# DRS4_ADC.net
KiCad netlist of a schematic drawn in Altium Designer
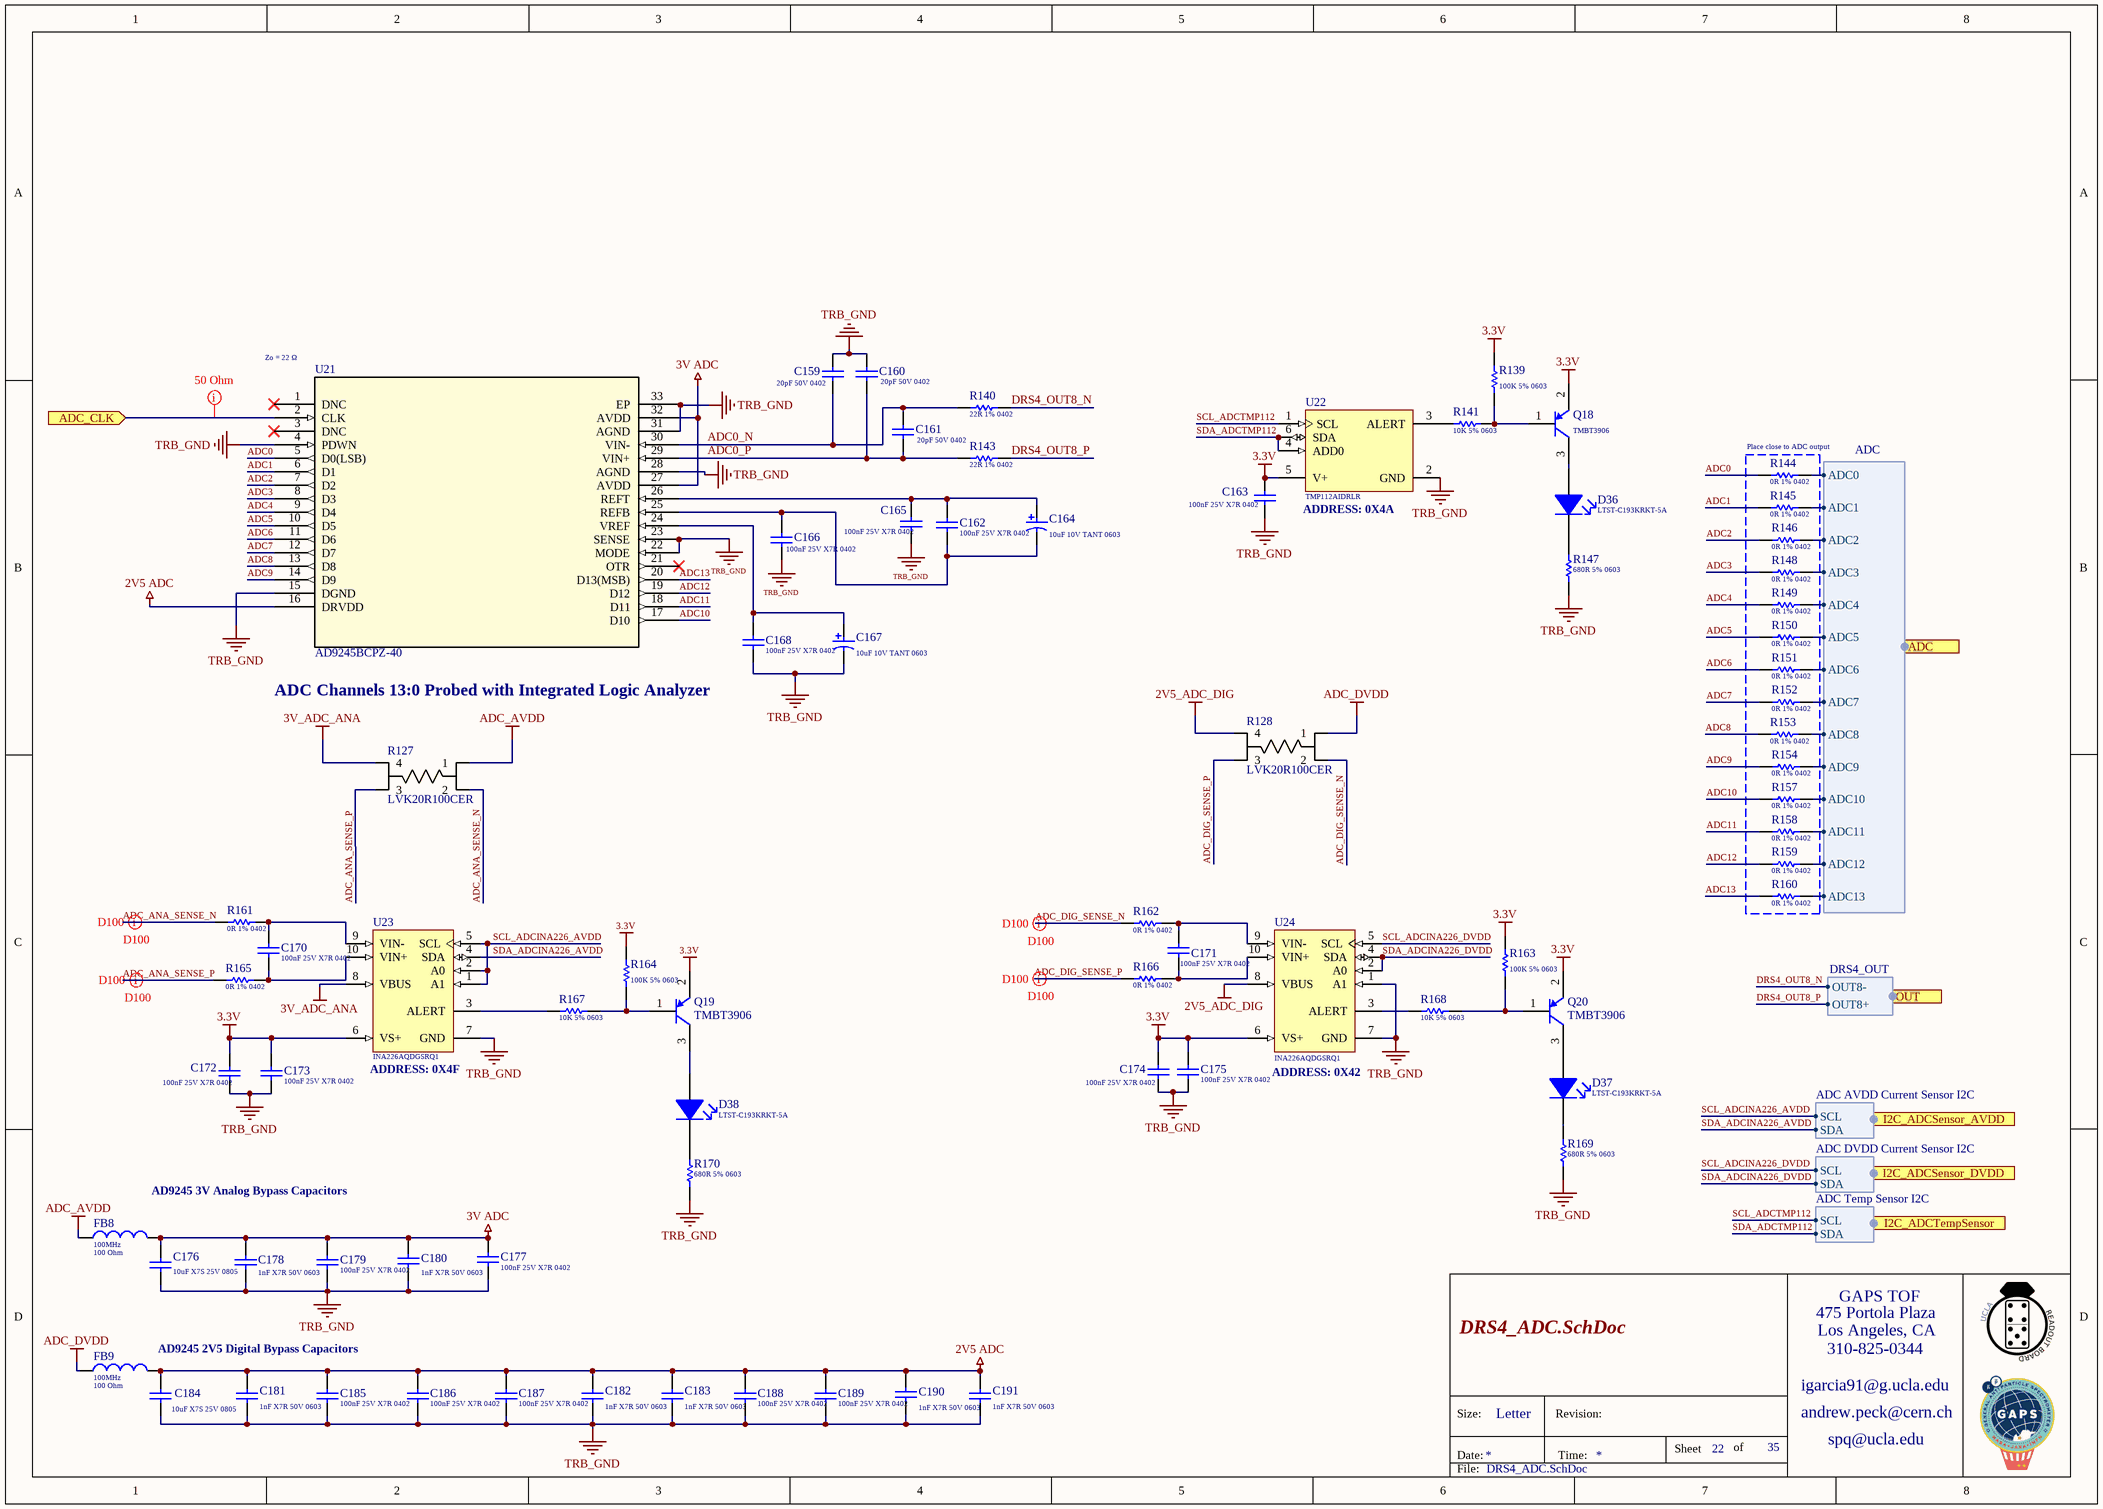
[diagram p0: DRS4_ADC.SchDoc]

(export (version "E")
  (design (tool "Eeschema 10.0.6"))
  (components
    (comp (ref "C159")
      (value "Cap_Murata_GJM1555C1H200GB01D_20pF")
      (footprint "Cap_Murata_GJM1555C1H200GB01D_20pF")
      (description "Multilayer Ceramic Capacitors MLCC - SMD/SMT 0402 20pF 50Volts C0G 2%")
      (fields (field (name "CAPACITANCE") "20pF 50V 0402"))
      (libsource (lib "Cap_Murata_GJM1555C1H200GB01D_20pF") (part "Cap_Murata_GJM1555C1H200GB01D_20pF"))
    )
    (comp (ref "C160")
      (value "Cap_Murata_GJM1555C1H200GB01D_20pF")
      (footprint "Cap_Murata_GJM1555C1H200GB01D_20pF")
      (description "Multilayer Ceramic Capacitors MLCC - SMD/SMT 0402 20pF 50Volts C0G 2%")
      (fields (field (name "CAPACITANCE") "20pF 50V 0402"))
      (libsource (lib "Cap_Murata_GJM1555C1H200GB01D_20pF") (part "Cap_Murata_GJM1555C1H200GB01D_20pF"))
    )
    (comp (ref "C161")
      (value "Cap_Murata_GJM1555C1H200GB01D_20pF")
      (footprint "Cap_Murata_GJM1555C1H200GB01D_20pF")
      (description "Multilayer Ceramic Capacitors MLCC - SMD/SMT 0402 20pF 50Volts C0G 2%")
      (fields (field (name "CAPACITANCE") "20pF 50V 0402"))
      (libsource (lib "Cap_Murata_GJM1555C1H200GB01D_20pF") (part "Cap_Murata_GJM1555C1H200GB01D_20pF"))
    )
    (comp (ref "C162")
      (value "Cap_Taiyo_Yuden_TMK105B7104KV-FR_100nF")
      (footprint "Cap_Taiyo_Yuden_TMK105B7104KV-FR_100nF")
      (description "CAP CER 100nF 25V X7R 0402")
      (fields (field (name "CAPACITANCE") "100nF 25V X7R 0402"))
      (libsource (lib "Cap_Taiyo_Yuden_TMK105B7104KV-FR_100nF") (part "Cap_Taiyo_Yuden_TMK105B7104KV-FR_100nF"))
    )
    (comp (ref "C163")
      (value "Cap_Taiyo_Yuden_TMK105B7104KV-FR_100nF")
      (footprint "Cap_Taiyo_Yuden_TMK105B7104KV-FR_100nF")
      (description "CAP CER 100nF 25V X7R 0402")
      (fields (field (name "CAPACITANCE") "100nF 25V X7R 0402"))
      (libsource (lib "Cap_Taiyo_Yuden_TMK105B7104KV-FR_100nF") (part "Cap_Taiyo_Yuden_TMK105B7104KV-FR_100nF"))
    )
    (comp (ref "C164")
      (value "10uF 10V TANT 0603")
      (footprint "VISH-TR8-M_L")
      (description "Tantalum Capacitor, 10 uF, +/- 20%, 10 V, -55 to 125 degC, 2-Pin SMD (M), RoHS, Tape and Reel")
      (fields (field (name "TOLERANCE") "±20%") (field (name "MANUFACTURER") "Vishay"))
      (libsource (lib "Altium Content Vault") (part "CAP-P-2"))
    )
    (comp (ref "C165")
      (value "Cap_Taiyo_Yuden_TMK105B7104KV-FR_100nF")
      (footprint "Cap_Taiyo_Yuden_TMK105B7104KV-FR_100nF")
      (description "CAP CER 100nF 25V X7R 0402")
      (fields (field (name "CAPACITANCE") "100nF 25V X7R 0402"))
      (libsource (lib "Cap_Taiyo_Yuden_TMK105B7104KV-FR_100nF") (part "Cap_Taiyo_Yuden_TMK105B7104KV-FR_100nF"))
    )
    (comp (ref "C166")
      (value "Cap_Taiyo_Yuden_TMK105B7104KV-FR_100nF")
      (footprint "Cap_Taiyo_Yuden_TMK105B7104KV-FR_100nF")
      (description "CAP CER 100nF 25V X7R 0402")
      (fields (field (name "CAPACITANCE") "100nF 25V X7R 0402"))
      (libsource (lib "Cap_Taiyo_Yuden_TMK105B7104KV-FR_100nF") (part "Cap_Taiyo_Yuden_TMK105B7104KV-FR_100nF"))
    )
    (comp (ref "C167")
      (value "10uF 10V TANT 0603")
      (footprint "VISH-TR8-M_L")
      (description "Tantalum Capacitor, 10 uF, +/- 20%, 10 V, -55 to 125 degC, 2-Pin SMD (M), RoHS, Tape and Reel")
      (fields (field (name "TOLERANCE") "±20%") (field (name "MANUFACTURER") "Vishay"))
      (libsource (lib "Altium Content Vault") (part "CAP-P-2"))
    )
    (comp (ref "C168")
      (value "Cap_Taiyo_Yuden_TMK105B7104KV-FR_100nF")
      (footprint "Cap_Taiyo_Yuden_TMK105B7104KV-FR_100nF")
      (description "CAP CER 100nF 25V X7R 0402")
      (fields (field (name "CAPACITANCE") "100nF 25V X7R 0402"))
      (libsource (lib "Cap_Taiyo_Yuden_TMK105B7104KV-FR_100nF") (part "Cap_Taiyo_Yuden_TMK105B7104KV-FR_100nF"))
    )
    (comp (ref "C170")
      (value "Cap_Taiyo_Yuden_TMK105B7104KV-FR_100nF")
      (footprint "Cap_Taiyo_Yuden_TMK105B7104KV-FR_100nF")
      (description "CAP CER 100nF 25V X7R 0402")
      (fields (field (name "CAPACITANCE") "100nF 25V X7R 0402"))
      (libsource (lib "Cap_Taiyo_Yuden_TMK105B7104KV-FR_100nF") (part "Cap_Taiyo_Yuden_TMK105B7104KV-FR_100nF"))
    )
    (comp (ref "C171")
      (value "Cap_Taiyo_Yuden_TMK105B7104KV-FR_100nF")
      (footprint "Cap_Taiyo_Yuden_TMK105B7104KV-FR_100nF")
      (description "CAP CER 100nF 25V X7R 0402")
      (fields (field (name "CAPACITANCE") "100nF 25V X7R 0402"))
      (libsource (lib "Cap_Taiyo_Yuden_TMK105B7104KV-FR_100nF") (part "Cap_Taiyo_Yuden_TMK105B7104KV-FR_100nF"))
    )
    (comp (ref "C172")
      (value "Cap_Taiyo_Yuden_TMK105B7104KV-FR_100nF")
      (footprint "Cap_Taiyo_Yuden_TMK105B7104KV-FR_100nF")
      (description "CAP CER 100nF 25V X7R 0402")
      (fields (field (name "CAPACITANCE") "100nF 25V X7R 0402"))
      (libsource (lib "Cap_Taiyo_Yuden_TMK105B7104KV-FR_100nF") (part "Cap_Taiyo_Yuden_TMK105B7104KV-FR_100nF"))
    )
    (comp (ref "C173")
      (value "Cap_Taiyo_Yuden_TMK105B7104KV-FR_100nF")
      (footprint "Cap_Taiyo_Yuden_TMK105B7104KV-FR_100nF")
      (description "CAP CER 100nF 25V X7R 0402")
      (fields (field (name "CAPACITANCE") "100nF 25V X7R 0402"))
      (libsource (lib "Cap_Taiyo_Yuden_TMK105B7104KV-FR_100nF") (part "Cap_Taiyo_Yuden_TMK105B7104KV-FR_100nF"))
    )
    (comp (ref "C174")
      (value "Cap_Taiyo_Yuden_TMK105B7104KV-FR_100nF")
      (footprint "Cap_Taiyo_Yuden_TMK105B7104KV-FR_100nF")
      (description "CAP CER 100nF 25V X7R 0402")
      (fields (field (name "CAPACITANCE") "100nF 25V X7R 0402"))
      (libsource (lib "Cap_Taiyo_Yuden_TMK105B7104KV-FR_100nF") (part "Cap_Taiyo_Yuden_TMK105B7104KV-FR_100nF"))
    )
    (comp (ref "C175")
      (value "Cap_Taiyo_Yuden_TMK105B7104KV-FR_100nF")
      (footprint "Cap_Taiyo_Yuden_TMK105B7104KV-FR_100nF")
      (description "CAP CER 100nF 25V X7R 0402")
      (fields (field (name "CAPACITANCE") "100nF 25V X7R 0402"))
      (libsource (lib "Cap_Taiyo_Yuden_TMK105B7104KV-FR_100nF") (part "Cap_Taiyo_Yuden_TMK105B7104KV-FR_100nF"))
    )
    (comp (ref "C176")
      (value "Cap_Murata_ GRM21BC71E106ME11L_10uF")
      (footprint "Cap_Murata_ GRM21BC71E106ME11L_10uF")
      (description "CAP CER 10uF 25V X7R 0805")
      (fields (field (name "CAPACITANCE") "10uF X7S 25V 0805"))
      (libsource (lib "Cap_Murata_ GRM21BC71E106ME11L_10uF") (part "Cap_Murata_ GRM21BC71E106ME11L_10uF"))
    )
    (comp (ref "C177")
      (value "Cap_Taiyo_Yuden_TMK105B7104KV-FR_100nF")
      (footprint "Cap_Taiyo_Yuden_TMK105B7104KV-FR_100nF")
      (description "CAP CER 100nF 25V X7R 0402")
      (fields (field (name "CAPACITANCE") "100nF 25V X7R 0402"))
      (libsource (lib "Cap_Taiyo_Yuden_TMK105B7104KV-FR_100nF") (part "Cap_Taiyo_Yuden_TMK105B7104KV-FR_100nF"))
    )
    (comp (ref "C178")
      (value "Cap_Kemet_C0603C102J5RACAUTO_1nF")
      (footprint "Cap_Kemet_C0603C102J5RACAUTO_1nF")
      (description "CAP CER 1nF 50V X7R 0603")
      (fields (field (name "CAPACITANCE") "1nF X7R 50V 0603"))
      (libsource (lib "Cap_Kemet_C0603C102J5RACAUTO_1nF") (part "Cap_Kemet_C0603C102J5RACAUTO_1nF"))
    )
    (comp (ref "C179")
      (value "Cap_Taiyo_Yuden_TMK105B7104KV-FR_100nF")
      (footprint "Cap_Taiyo_Yuden_TMK105B7104KV-FR_100nF")
      (description "CAP CER 100nF 25V X7R 0402")
      (fields (field (name "CAPACITANCE") "100nF 25V X7R 0402"))
      (libsource (lib "Cap_Taiyo_Yuden_TMK105B7104KV-FR_100nF") (part "Cap_Taiyo_Yuden_TMK105B7104KV-FR_100nF"))
    )
    (comp (ref "C180")
      (value "Cap_Kemet_C0603C102J5RACAUTO_1nF")
      (footprint "Cap_Kemet_C0603C102J5RACAUTO_1nF")
      (description "CAP CER 1nF 50V X7R 0603")
      (fields (field (name "CAPACITANCE") "1nF X7R 50V 0603"))
      (libsource (lib "Cap_Kemet_C0603C102J5RACAUTO_1nF") (part "Cap_Kemet_C0603C102J5RACAUTO_1nF"))
    )
    (comp (ref "C181")
      (value "Cap_Kemet_C0603C102J5RACAUTO_1nF")
      (footprint "Cap_Kemet_C0603C102J5RACAUTO_1nF")
      (description "CAP CER 1nF 50V X7R 0603")
      (fields (field (name "CAPACITANCE") "1nF X7R 50V 0603"))
      (libsource (lib "Cap_Kemet_C0603C102J5RACAUTO_1nF") (part "Cap_Kemet_C0603C102J5RACAUTO_1nF"))
    )
    (comp (ref "C182")
      (value "Cap_Kemet_C0603C102J5RACAUTO_1nF")
      (footprint "Cap_Kemet_C0603C102J5RACAUTO_1nF")
      (description "CAP CER 1nF 50V X7R 0603")
      (fields (field (name "CAPACITANCE") "1nF X7R 50V 0603"))
      (libsource (lib "Cap_Kemet_C0603C102J5RACAUTO_1nF") (part "Cap_Kemet_C0603C102J5RACAUTO_1nF"))
    )
    (comp (ref "C183")
      (value "Cap_Kemet_C0603C102J5RACAUTO_1nF")
      (footprint "Cap_Kemet_C0603C102J5RACAUTO_1nF")
      (description "CAP CER 1nF 50V X7R 0603")
      (fields (field (name "CAPACITANCE") "1nF X7R 50V 0603"))
      (libsource (lib "Cap_Kemet_C0603C102J5RACAUTO_1nF") (part "Cap_Kemet_C0603C102J5RACAUTO_1nF"))
    )
    (comp (ref "C184")
      (value "Cap_Murata_ GRM21BC71E106ME11L_10uF")
      (footprint "Cap_Murata_ GRM21BC71E106ME11L_10uF")
      (description "CAP CER 10uF 25V X7R 0805")
      (fields (field (name "CAPACITANCE") "10uF X7S 25V 0805"))
      (libsource (lib "Cap_Murata_ GRM21BC71E106ME11L_10uF") (part "Cap_Murata_ GRM21BC71E106ME11L_10uF"))
    )
    (comp (ref "C185")
      (value "Cap_Taiyo_Yuden_TMK105B7104KV-FR_100nF")
      (footprint "Cap_Taiyo_Yuden_TMK105B7104KV-FR_100nF")
      (description "CAP CER 100nF 25V X7R 0402")
      (fields (field (name "CAPACITANCE") "100nF 25V X7R 0402"))
      (libsource (lib "Cap_Taiyo_Yuden_TMK105B7104KV-FR_100nF") (part "Cap_Taiyo_Yuden_TMK105B7104KV-FR_100nF"))
    )
    (comp (ref "C186")
      (value "Cap_Taiyo_Yuden_TMK105B7104KV-FR_100nF")
      (footprint "Cap_Taiyo_Yuden_TMK105B7104KV-FR_100nF")
      (description "CAP CER 100nF 25V X7R 0402")
      (fields (field (name "CAPACITANCE") "100nF 25V X7R 0402"))
      (libsource (lib "Cap_Taiyo_Yuden_TMK105B7104KV-FR_100nF") (part "Cap_Taiyo_Yuden_TMK105B7104KV-FR_100nF"))
    )
    (comp (ref "C187")
      (value "Cap_Taiyo_Yuden_TMK105B7104KV-FR_100nF")
      (footprint "Cap_Taiyo_Yuden_TMK105B7104KV-FR_100nF")
      (description "CAP CER 100nF 25V X7R 0402")
      (fields (field (name "CAPACITANCE") "100nF 25V X7R 0402"))
      (libsource (lib "Cap_Taiyo_Yuden_TMK105B7104KV-FR_100nF") (part "Cap_Taiyo_Yuden_TMK105B7104KV-FR_100nF"))
    )
    (comp (ref "C188")
      (value "Cap_Taiyo_Yuden_TMK105B7104KV-FR_100nF")
      (footprint "Cap_Taiyo_Yuden_TMK105B7104KV-FR_100nF")
      (description "CAP CER 100nF 25V X7R 0402")
      (fields (field (name "CAPACITANCE") "100nF 25V X7R 0402"))
      (libsource (lib "Cap_Taiyo_Yuden_TMK105B7104KV-FR_100nF") (part "Cap_Taiyo_Yuden_TMK105B7104KV-FR_100nF"))
    )
    (comp (ref "C189")
      (value "Cap_Taiyo_Yuden_TMK105B7104KV-FR_100nF")
      (footprint "Cap_Taiyo_Yuden_TMK105B7104KV-FR_100nF")
      (description "CAP CER 100nF 25V X7R 0402")
      (fields (field (name "CAPACITANCE") "100nF 25V X7R 0402"))
      (libsource (lib "Cap_Taiyo_Yuden_TMK105B7104KV-FR_100nF") (part "Cap_Taiyo_Yuden_TMK105B7104KV-FR_100nF"))
    )
    (comp (ref "C190")
      (value "Cap_Kemet_C0603C102J5RACAUTO_1nF")
      (footprint "Cap_Kemet_C0603C102J5RACAUTO_1nF")
      (description "CAP CER 1nF 50V X7R 0603")
      (fields (field (name "CAPACITANCE") "1nF X7R 50V 0603"))
      (libsource (lib "Cap_Kemet_C0603C102J5RACAUTO_1nF") (part "Cap_Kemet_C0603C102J5RACAUTO_1nF"))
    )
    (comp (ref "C191")
      (value "Cap_Kemet_C0603C102J5RACAUTO_1nF")
      (footprint "Cap_Kemet_C0603C102J5RACAUTO_1nF")
      (description "CAP CER 1nF 50V X7R 0603")
      (fields (field (name "CAPACITANCE") "1nF X7R 50V 0603"))
      (libsource (lib "Cap_Kemet_C0603C102J5RACAUTO_1nF") (part "Cap_Kemet_C0603C102J5RACAUTO_1nF"))
    )
    (comp (ref "D36")
      (value "LTST-C193KRKT-5A")
      (footprint "Led_Lite-On_LTST-C193KGKT-5A_Red")
      (description "Standard LEDs - SMD Red 470nm 28mcd 20mA")
      (fields (field (name "SERIES") "LTST-C193KRKT-5A"))
      (libsource (lib "Led_Lite-On_LTST-C193KGKT-5A_Red") (part "Led_Lite-On_LTST-C193KGKT-5A_Red"))
    )
    (comp (ref "D37")
      (value "LTST-C193KRKT-5A")
      (footprint "Led_Lite-On_LTST-C193KGKT-5A_Red")
      (description "Standard LEDs - SMD Red 470nm 28mcd 20mA")
      (fields (field (name "SERIES") "LTST-C193KRKT-5A"))
      (libsource (lib "Led_Lite-On_LTST-C193KGKT-5A_Red") (part "Led_Lite-On_LTST-C193KGKT-5A_Red"))
    )
    (comp (ref "D38")
      (value "LTST-C193KRKT-5A")
      (footprint "Led_Lite-On_LTST-C193KGKT-5A_Red")
      (description "Standard LEDs - SMD Red 470nm 28mcd 20mA")
      (fields (field (name "SERIES") "LTST-C193KRKT-5A"))
      (libsource (lib "Led_Lite-On_LTST-C193KGKT-5A_Red") (part "Led_Lite-On_LTST-C193KGKT-5A_Red"))
    )
    (comp (ref "FB8")
      (value "742792731")
      (footprint "FB_Wurth_Electronics_742792731_100Ohms")
      (description "FB SMD 100 OHM 25% 1.2A 0402")
      (fields (field (name "MEASURING FREQUENCY") "100MHz") (field (name "IMPEDANCE") "100 Ohm"))
      (libsource (lib "FB_Wurth_Electronics_742792731_100Ohms") (part "FB_Wurth_Electronics_742792731_100Ohms"))
    )
    (comp (ref "FB9")
      (value "742792731")
      (footprint "FB_Wurth_Electronics_742792731_100Ohms")
      (description "FB SMD 100 OHM 25% 1.2A 0402")
      (fields (field (name "MEASURING FREQUENCY") "100MHz") (field (name "IMPEDANCE") "100 Ohm"))
      (libsource (lib "FB_Wurth_Electronics_742792731_100Ohms") (part "FB_Wurth_Electronics_742792731_100Ohms"))
    )
    (comp (ref "Q18")
      (value "BJT_PNP_Toshiba_TMBT3906")
      (footprint "BJT_PNP_Toshiba_TMBT3906")
      (description "Bipolar Transistors - BJT Transistor for Low Freq. Amplification")
      (fields (field (name "SERIES") "TMBT3906") (field (name "MANUFACTURER") "Toshiba"))
      (libsource (lib "BJT_PNP_Toshiba_TMBT3906") (part "BJT_PNP_Toshiba_TMBT3906"))
    )
    (comp (ref "Q19")
      (value "BJT_PNP_Toshiba_TMBT3906")
      (footprint "BJT_PNP_Toshiba_TMBT3906")
      (description "Bipolar Transistors - BJT Transistor for Low Freq. Amplification")
      (fields (field (name "SERIES") "TMBT3906") (field (name "MANUFACTURER") "Toshiba"))
      (libsource (lib "BJT_PNP_Toshiba_TMBT3906") (part "BJT_PNP_Toshiba_TMBT3906"))
    )
    (comp (ref "Q20")
      (value "BJT_PNP_Toshiba_TMBT3906")
      (footprint "BJT_PNP_Toshiba_TMBT3906")
      (description "Bipolar Transistors - BJT Transistor for Low Freq. Amplification")
      (fields (field (name "SERIES") "TMBT3906") (field (name "MANUFACTURER") "Toshiba"))
      (libsource (lib "BJT_PNP_Toshiba_TMBT3906") (part "BJT_PNP_Toshiba_TMBT3906"))
    )
    (comp (ref "R127")
      (value "LVK20R100CER")
      (footprint "OH_LVK20_OHM")
      (description "Current Sense Resistors - SMD .1 OHM.25% 3/4W")
      (fields (field (name "COPYRIGHT") "Copyright (C) 2018 Accelerated Designs. All rights reserved"))
      (libsource (lib "Shunt_Res_Ohmite_LVK20R100CER") (part "LVK20R100CER"))
    )
    (comp (ref "R128")
      (value "LVK20R100CER")
      (footprint "OH_LVK20_OHM")
      (description "Current Sense Resistors - SMD .1 OHM.25% 3/4W")
      (fields (field (name "COPYRIGHT") "Copyright (C) 2018 Accelerated Designs. All rights reserved"))
      (libsource (lib "Shunt_Res_Ohmite_LVK20R100CER") (part "LVK20R100CER"))
    )
    (comp (ref "R139")
      (value "100K 5% 0603")
      (footprint "RESC0603(1608)_N")
      (description "100K 0.1W 5% 0603 (1608 Metric)  SMD")
      (fields (field (name "TOLERANCE") "5 %") (field (name "POWER") "0.1 W"))
      (libsource (lib "Altium Content Vault") (part "RES"))
    )
    (comp (ref "R140")
      (value "22R 1% 0402")
      (footprint "RESC0402(1005)_L")
      (description "22R 0.063W 1% 0402 (1005 Metric)  SMD")
      (fields (field (name "TOLERANCE") "1 %") (field (name "POWER") "0.063 W"))
      (libsource (lib "Altium Content Vault") (part "RES"))
    )
    (comp (ref "R141")
      (value "10K 5% 0603")
      (footprint "RESC0603(1608)_L")
      (description "10K 0.1W 5% 0603 (1608 Metric)  SMD")
      (fields (field (name "TOLERANCE") "5 %") (field (name "POWER") "0.1 W"))
      (libsource (lib "Altium Content Vault") (part "RES"))
    )
    (comp (ref "R143")
      (value "22R 1% 0402")
      (footprint "RESC0402(1005)_L")
      (description "22R 0.063W 1% 0402 (1005 Metric)  SMD")
      (fields (field (name "TOLERANCE") "1 %") (field (name "POWER") "0.063 W"))
      (libsource (lib "Altium Content Vault") (part "RES"))
    )
    (comp (ref "R144")
      (value "Res_Vishay_CRCW04020000Z0EDC_0_Ohm")
      (footprint "Res_Vishay_CRCW04020000Z0EDC_0_Ohm")
      (description "0R 0.062W 1% 0402 (1005 Metric)  SMD")
      (fields (field (name "RESISTANCE") "0R 1% 0402"))
      (libsource (lib "Res_Vishay_CRCW04020000Z0EDC_0_Ohm") (part "Res_Vishay_CRCW04020000Z0EDC_0_Ohm"))
    )
    (comp (ref "R145")
      (value "Res_Vishay_CRCW04020000Z0EDC_0_Ohm")
      (footprint "Res_Vishay_CRCW04020000Z0EDC_0_Ohm")
      (description "0R 0.062W 1% 0402 (1005 Metric)  SMD")
      (fields (field (name "RESISTANCE") "0R 1% 0402"))
      (libsource (lib "Res_Vishay_CRCW04020000Z0EDC_0_Ohm") (part "Res_Vishay_CRCW04020000Z0EDC_0_Ohm"))
    )
    (comp (ref "R146")
      (value "Res_Vishay_CRCW04020000Z0EDC_0_Ohm")
      (footprint "Res_Vishay_CRCW04020000Z0EDC_0_Ohm")
      (description "0R 0.062W 1% 0402 (1005 Metric)  SMD")
      (fields (field (name "RESISTANCE") "0R 1% 0402"))
      (libsource (lib "Res_Vishay_CRCW04020000Z0EDC_0_Ohm") (part "Res_Vishay_CRCW04020000Z0EDC_0_Ohm"))
    )
    (comp (ref "R147")
      (value "680R 5% 0603")
      (footprint "RESC0603(1608)_L")
      (description "680R 0.1W 5% 0603 (1608 Metric)  SMD")
      (fields (field (name "TOLERANCE") "5 %") (field (name "POWER") "0.1 W"))
      (libsource (lib "Altium Content Vault") (part "RES"))
    )
    (comp (ref "R148")
      (value "Res_Vishay_CRCW04020000Z0EDC_0_Ohm")
      (footprint "Res_Vishay_CRCW04020000Z0EDC_0_Ohm")
      (description "0R 0.062W 1% 0402 (1005 Metric)  SMD")
      (fields (field (name "RESISTANCE") "0R 1% 0402"))
      (libsource (lib "Res_Vishay_CRCW04020000Z0EDC_0_Ohm") (part "Res_Vishay_CRCW04020000Z0EDC_0_Ohm"))
    )
    (comp (ref "R149")
      (value "Res_Vishay_CRCW04020000Z0EDC_0_Ohm")
      (footprint "Res_Vishay_CRCW04020000Z0EDC_0_Ohm")
      (description "0R 0.062W 1% 0402 (1005 Metric)  SMD")
      (fields (field (name "RESISTANCE") "0R 1% 0402"))
      (libsource (lib "Res_Vishay_CRCW04020000Z0EDC_0_Ohm") (part "Res_Vishay_CRCW04020000Z0EDC_0_Ohm"))
    )
    (comp (ref "R150")
      (value "Res_Vishay_CRCW04020000Z0EDC_0_Ohm")
      (footprint "Res_Vishay_CRCW04020000Z0EDC_0_Ohm")
      (description "0R 0.062W 1% 0402 (1005 Metric)  SMD")
      (fields (field (name "RESISTANCE") "0R 1% 0402"))
      (libsource (lib "Res_Vishay_CRCW04020000Z0EDC_0_Ohm") (part "Res_Vishay_CRCW04020000Z0EDC_0_Ohm"))
    )
    (comp (ref "R151")
      (value "Res_Vishay_CRCW04020000Z0EDC_0_Ohm")
      (footprint "Res_Vishay_CRCW04020000Z0EDC_0_Ohm")
      (description "0R 0.062W 1% 0402 (1005 Metric)  SMD")
      (fields (field (name "RESISTANCE") "0R 1% 0402"))
      (libsource (lib "Res_Vishay_CRCW04020000Z0EDC_0_Ohm") (part "Res_Vishay_CRCW04020000Z0EDC_0_Ohm"))
    )
    (comp (ref "R152")
      (value "Res_Vishay_CRCW04020000Z0EDC_0_Ohm")
      (footprint "Res_Vishay_CRCW04020000Z0EDC_0_Ohm")
      (description "0R 0.062W 1% 0402 (1005 Metric)  SMD")
      (fields (field (name "RESISTANCE") "0R 1% 0402"))
      (libsource (lib "Res_Vishay_CRCW04020000Z0EDC_0_Ohm") (part "Res_Vishay_CRCW04020000Z0EDC_0_Ohm"))
    )
    (comp (ref "R153")
      (value "Res_Vishay_CRCW04020000Z0EDC_0_Ohm")
      (footprint "Res_Vishay_CRCW04020000Z0EDC_0_Ohm")
      (description "0R 0.062W 1% 0402 (1005 Metric)  SMD")
      (fields (field (name "RESISTANCE") "0R 1% 0402"))
      (libsource (lib "Res_Vishay_CRCW04020000Z0EDC_0_Ohm") (part "Res_Vishay_CRCW04020000Z0EDC_0_Ohm"))
    )
    (comp (ref "R154")
      (value "Res_Vishay_CRCW04020000Z0EDC_0_Ohm")
      (footprint "Res_Vishay_CRCW04020000Z0EDC_0_Ohm")
      (description "0R 0.062W 1% 0402 (1005 Metric)  SMD")
      (fields (field (name "RESISTANCE") "0R 1% 0402"))
      (libsource (lib "Res_Vishay_CRCW04020000Z0EDC_0_Ohm") (part "Res_Vishay_CRCW04020000Z0EDC_0_Ohm"))
    )
    (comp (ref "R157")
      (value "Res_Vishay_CRCW04020000Z0EDC_0_Ohm")
      (footprint "Res_Vishay_CRCW04020000Z0EDC_0_Ohm")
      (description "0R 0.062W 1% 0402 (1005 Metric)  SMD")
      (fields (field (name "RESISTANCE") "0R 1% 0402"))
      (libsource (lib "Res_Vishay_CRCW04020000Z0EDC_0_Ohm") (part "Res_Vishay_CRCW04020000Z0EDC_0_Ohm"))
    )
    (comp (ref "R158")
      (value "Res_Vishay_CRCW04020000Z0EDC_0_Ohm")
      (footprint "Res_Vishay_CRCW04020000Z0EDC_0_Ohm")
      (description "0R 0.062W 1% 0402 (1005 Metric)  SMD")
      (fields (field (name "RESISTANCE") "0R 1% 0402"))
      (libsource (lib "Res_Vishay_CRCW04020000Z0EDC_0_Ohm") (part "Res_Vishay_CRCW04020000Z0EDC_0_Ohm"))
    )
    (comp (ref "R159")
      (value "Res_Vishay_CRCW04020000Z0EDC_0_Ohm")
      (footprint "Res_Vishay_CRCW04020000Z0EDC_0_Ohm")
      (description "0R 0.062W 1% 0402 (1005 Metric)  SMD")
      (fields (field (name "RESISTANCE") "0R 1% 0402"))
      (libsource (lib "Res_Vishay_CRCW04020000Z0EDC_0_Ohm") (part "Res_Vishay_CRCW04020000Z0EDC_0_Ohm"))
    )
    (comp (ref "R160")
      (value "Res_Vishay_CRCW04020000Z0EDC_0_Ohm")
      (footprint "Res_Vishay_CRCW04020000Z0EDC_0_Ohm")
      (description "0R 0.062W 1% 0402 (1005 Metric)  SMD")
      (fields (field (name "RESISTANCE") "0R 1% 0402"))
      (libsource (lib "Res_Vishay_CRCW04020000Z0EDC_0_Ohm") (part "Res_Vishay_CRCW04020000Z0EDC_0_Ohm"))
    )
    (comp (ref "R161")
      (value "Res_Vishay_CRCW04020000Z0EDC_0_Ohm")
      (footprint "Res_Vishay_CRCW04020000Z0EDC_0_Ohm")
      (description "0R 0.062W 1% 0402 (1005 Metric)  SMD")
      (fields (field (name "RESISTANCE") "0R 1% 0402"))
      (libsource (lib "Res_Vishay_CRCW04020000Z0EDC_0_Ohm") (part "Res_Vishay_CRCW04020000Z0EDC_0_Ohm"))
    )
    (comp (ref "R162")
      (value "Res_Vishay_CRCW04020000Z0EDC_0_Ohm")
      (footprint "Res_Vishay_CRCW04020000Z0EDC_0_Ohm")
      (description "0R 0.062W 1% 0402 (1005 Metric)  SMD")
      (fields (field (name "RESISTANCE") "0R 1% 0402"))
      (libsource (lib "Res_Vishay_CRCW04020000Z0EDC_0_Ohm") (part "Res_Vishay_CRCW04020000Z0EDC_0_Ohm"))
    )
    (comp (ref "R163")
      (value "100K 5% 0603")
      (footprint "RESC0603(1608)_N")
      (description "100K 0.1W 5% 0603 (1608 Metric)  SMD")
      (fields (field (name "TOLERANCE") "5 %") (field (name "POWER") "0.1 W"))
      (libsource (lib "Altium Content Vault") (part "RES"))
    )
    (comp (ref "R164")
      (value "100K 5% 0603")
      (footprint "RESC0603(1608)_N")
      (description "100K 0.1W 5% 0603 (1608 Metric)  SMD")
      (fields (field (name "TOLERANCE") "5 %") (field (name "POWER") "0.1 W"))
      (libsource (lib "Altium Content Vault") (part "RES"))
    )
    (comp (ref "R165")
      (value "Res_Vishay_CRCW04020000Z0EDC_0_Ohm")
      (footprint "Res_Vishay_CRCW04020000Z0EDC_0_Ohm")
      (description "0R 0.062W 1% 0402 (1005 Metric)  SMD")
      (fields (field (name "RESISTANCE") "0R 1% 0402"))
      (libsource (lib "Res_Vishay_CRCW04020000Z0EDC_0_Ohm") (part "Res_Vishay_CRCW04020000Z0EDC_0_Ohm"))
    )
    (comp (ref "R166")
      (value "Res_Vishay_CRCW04020000Z0EDC_0_Ohm")
      (footprint "Res_Vishay_CRCW04020000Z0EDC_0_Ohm")
      (description "0R 0.062W 1% 0402 (1005 Metric)  SMD")
      (fields (field (name "RESISTANCE") "0R 1% 0402"))
      (libsource (lib "Res_Vishay_CRCW04020000Z0EDC_0_Ohm") (part "Res_Vishay_CRCW04020000Z0EDC_0_Ohm"))
    )
    (comp (ref "R167")
      (value "10K 5% 0603")
      (footprint "RESC0603(1608)_L")
      (description "10K 0.1W 5% 0603 (1608 Metric)  SMD")
      (fields (field (name "TOLERANCE") "5 %") (field (name "POWER") "0.1 W"))
      (libsource (lib "Altium Content Vault") (part "RES"))
    )
    (comp (ref "R168")
      (value "10K 5% 0603")
      (footprint "RESC0603(1608)_L")
      (description "10K 0.1W 5% 0603 (1608 Metric)  SMD")
      (fields (field (name "TOLERANCE") "5 %") (field (name "POWER") "0.1 W"))
      (libsource (lib "Altium Content Vault") (part "RES"))
    )
    (comp (ref "R169")
      (value "680R 5% 0603")
      (footprint "RESC0603(1608)_L")
      (description "680R 0.1W 5% 0603 (1608 Metric)  SMD")
      (fields (field (name "TOLERANCE") "5 %") (field (name "POWER") "0.1 W"))
      (libsource (lib "Altium Content Vault") (part "RES"))
    )
    (comp (ref "R170")
      (value "680R 5% 0603")
      (footprint "RESC0603(1608)_L")
      (description "680R 0.1W 5% 0603 (1608 Metric)  SMD")
      (fields (field (name "TOLERANCE") "5 %") (field (name "POWER") "0.1 W"))
      (libsource (lib "Altium Content Vault") (part "RES"))
    )
    (comp (ref "U21")
      (value "AD9245")
      (footprint "CP_32_2")
      (description "Analog to Digital Converters - ADC 14-Bit 40 MSPS 3V")
      (fields (field (name "SERIES") "AD9245BCPZ-40") (field (name "PART") "AD9245BCPZ-40"))
      (libsource (lib "AD9245BCPZ-40") (part "AD9245BCPZ-40"))
    )
    (comp (ref "U22")
      (value "TMP112AIDRLR")
      (footprint "TMP112AIDRLR")
      (description "Board Mount Temperature Sensors Hi-Prec Lo-Pwr Dig Temp Sensor")
      (libsource (lib "TMP112AIDRLR") (part "TMP112AIDRLR"))
    )
    (comp (ref "U23")
      (value "INA226AQDGSRQ1")
      (footprint "INA226AQDGSRQ1")
      (libsource (lib "INA226AQDGSRQ1") (part "INA226AQDGSRQ1"))
    )
    (comp (ref "U24")
      (value "INA226AQDGSRQ1")
      (footprint "INA226AQDGSRQ1")
      (libsource (lib "INA226AQDGSRQ1") (part "INA226AQDGSRQ1"))
    )
  )
  (nets
    (net (code "9") (name "/ADC0") (class "Default")
      (node (ref "R144") (pin "1") (pinfunction "1_1") (pintype "passive"))
      (node (ref "U21") (pin "5") (pinfunction "D0(LSB)_5") (pintype "output"))
    )
    (net (code "10") (name "/ADC0_N") (class "Default")
      (node (ref "C159") (pin "1") (pinfunction "1_1") (pintype "passive"))
      (node (ref "C161") (pin "2") (pinfunction "2_2") (pintype "passive"))
      (node (ref "R140") (pin "2") (pinfunction "2_2") (pintype "passive"))
      (node (ref "U21") (pin "30") (pinfunction "VIN-_30") (pintype "input"))
    )
    (net (code "11") (name "/ADC0_P") (class "Default")
      (node (ref "C160") (pin "1") (pinfunction "1_1") (pintype "passive"))
      (node (ref "C161") (pin "1") (pinfunction "1_1") (pintype "passive"))
      (node (ref "R143") (pin "2") (pinfunction "2_2") (pintype "passive"))
      (node (ref "U21") (pin "29") (pinfunction "VIN+_29") (pintype "input"))
    )
    (net (code "12") (name "/ADC1") (class "Default")
      (node (ref "R145") (pin "1") (pinfunction "1_1") (pintype "passive"))
      (node (ref "U21") (pin "6") (pinfunction "D1_6") (pintype "output"))
    )
    (net (code "13") (name "/ADC2") (class "Default")
      (node (ref "R146") (pin "1") (pinfunction "1_1") (pintype "passive"))
      (node (ref "U21") (pin "7") (pinfunction "D2_7") (pintype "output"))
    )
    (net (code "14") (name "/ADC3") (class "Default")
      (node (ref "R148") (pin "1") (pinfunction "1_1") (pintype "passive"))
      (node (ref "U21") (pin "8") (pinfunction "D3_8") (pintype "output"))
    )
    (net (code "15") (name "/ADC4") (class "Default")
      (node (ref "R149") (pin "1") (pinfunction "1_1") (pintype "passive"))
      (node (ref "U21") (pin "9") (pinfunction "D4_9") (pintype "output"))
    )
    (net (code "16") (name "/ADC5") (class "Default")
      (node (ref "R150") (pin "1") (pinfunction "1_1") (pintype "passive"))
      (node (ref "U21") (pin "10") (pinfunction "D5_10") (pintype "output"))
    )
    (net (code "17") (name "/ADC6") (class "Default")
      (node (ref "R151") (pin "1") (pinfunction "1_1") (pintype "passive"))
      (node (ref "U21") (pin "11") (pinfunction "D6_11") (pintype "output"))
    )
    (net (code "18") (name "/ADC7") (class "Default")
      (node (ref "R152") (pin "1") (pinfunction "1_1") (pintype "passive"))
      (node (ref "U21") (pin "12") (pinfunction "D7_12") (pintype "output"))
    )
    (net (code "19") (name "/ADC8") (class "Default")
      (node (ref "R153") (pin "1") (pinfunction "1_1") (pintype "passive"))
      (node (ref "U21") (pin "13") (pinfunction "D8_13") (pintype "output"))
    )
    (net (code "20") (name "/ADC9") (class "Default")
      (node (ref "R154") (pin "1") (pinfunction "1_1") (pintype "passive"))
      (node (ref "U21") (pin "14") (pinfunction "D9_14") (pintype "output"))
    )
    (net (code "21") (name "/ADC10") (class "Default")
      (node (ref "R157") (pin "1") (pinfunction "1_1") (pintype "passive"))
      (node (ref "U21") (pin "17") (pinfunction "D10_17") (pintype "output"))
    )
    (net (code "22") (name "/ADC11") (class "Default")
      (node (ref "R158") (pin "1") (pinfunction "1_1") (pintype "passive"))
      (node (ref "U21") (pin "18") (pinfunction "D11_18") (pintype "output"))
    )
    (net (code "23") (name "/ADC12") (class "Default")
      (node (ref "R159") (pin "1") (pinfunction "1_1") (pintype "passive"))
      (node (ref "U21") (pin "19") (pinfunction "D12_19") (pintype "output"))
    )
    (net (code "24") (name "/ADC13") (class "Default")
      (node (ref "R160") (pin "1") (pinfunction "1_1") (pintype "passive"))
      (node (ref "U21") (pin "20") (pinfunction "D13(MSB)_20") (pintype "output"))
    )
    (net (code "25") (name "/ADC_ANA_SENSE_N") (class "Default")
      (node (ref "R127") (pin "2") (pinfunction "2_2") (pintype "passive"))
      (node (ref "R161") (pin "1") (pinfunction "1_1") (pintype "passive"))
    )
    (net (code "26") (name "/ADC_ANA_SENSE_P") (class "Default")
      (node (ref "R127") (pin "3") (pinfunction "3_3") (pintype "passive"))
      (node (ref "R165") (pin "1") (pinfunction "1_1") (pintype "passive"))
    )
    (net (code "27") (name "/ADC_CLK") (class "Default")
      (node (ref "U21") (pin "2") (pinfunction "CLK_2") (pintype "input"))
    )
    (net (code "28") (name "/ADC_DIG_SENSE_N") (class "Default")
      (node (ref "R128") (pin "2") (pinfunction "2_2") (pintype "passive"))
      (node (ref "R162") (pin "1") (pinfunction "1_1") (pintype "passive"))
    )
    (net (code "29") (name "/ADC_DIG_SENSE_P") (class "Default")
      (node (ref "R128") (pin "3") (pinfunction "3_3") (pintype "passive"))
      (node (ref "R166") (pin "1") (pinfunction "1_1") (pintype "passive"))
    )
    (net (code "30") (name "/DRS4_OUT8_N") (class "Default")
      (node (ref "R140") (pin "1") (pinfunction "1_1") (pintype "passive"))
    )
    (net (code "31") (name "/DRS4_OUT8_P") (class "Default")
      (node (ref "R143") (pin "1") (pinfunction "1_1") (pintype "passive"))
    )
    (net (code "32") (name "/SCL_ADCINA226_AVDD") (class "Default")
      (node (ref "U23") (pin "1") (pinfunction "A1_1") (pintype "input"))
      (node (ref "U23") (pin "2") (pinfunction "A0_2") (pintype "input"))
      (node (ref "U23") (pin "5") (pinfunction "SCL_5") (pintype "input"))
    )
    (net (code "33") (name "/SCL_ADCINA226_DVDD") (class "Default")
      (node (ref "U24") (pin "5") (pinfunction "SCL_5") (pintype "input"))
    )
    (net (code "34") (name "/SCL_ADCTMP112") (class "Default")
      (node (ref "U22") (pin "1") (pinfunction "SCL_1") (pintype "input"))
    )
    (net (code "35") (name "/SDA_ADCINA226_AVDD") (class "Default")
      (node (ref "U23") (pin "4") (pinfunction "SDA_4") (pintype "bidirectional"))
    )
    (net (code "36") (name "/SDA_ADCINA226_DVDD") (class "Default")
      (node (ref "U24") (pin "2") (pinfunction "A0_2") (pintype "input"))
      (node (ref "U24") (pin "4") (pinfunction "SDA_4") (pintype "bidirectional"))
    )
    (net (code "37") (name "/SDA_ADCTMP112") (class "Default")
      (node (ref "U22") (pin "4") (pinfunction "ADD0_4") (pintype "input"))
      (node (ref "U22") (pin "6") (pinfunction "SDA_6") (pintype "bidirectional"))
    )
    (net (code "43") (name "2V5 ADC") (class "Default")
      (node (ref "C181") (pin "2") (pinfunction "2_2") (pintype "passive"))
      (node (ref "C182") (pin "2") (pinfunction "2_2") (pintype "passive"))
      (node (ref "C183") (pin "2") (pinfunction "2_2") (pintype "passive"))
      (node (ref "C184") (pin "1") (pinfunction "1_1") (pintype "passive"))
      (node (ref "C185") (pin "1") (pinfunction "1_1") (pintype "passive"))
      (node (ref "C186") (pin "1") (pinfunction "1_1") (pintype "passive"))
      (node (ref "C187") (pin "1") (pinfunction "1_1") (pintype "passive"))
      (node (ref "C188") (pin "1") (pinfunction "1_1") (pintype "passive"))
      (node (ref "C189") (pin "1") (pinfunction "1_1") (pintype "passive"))
      (node (ref "C190") (pin "2") (pinfunction "2_2") (pintype "passive"))
      (node (ref "C191") (pin "2") (pinfunction "2_2") (pintype "passive"))
      (node (ref "FB9") (pin "2") (pinfunction "2_2") (pintype "passive"))
      (node (ref "U21") (pin "16") (pinfunction "DRVDD_16") (pintype "power_in"))
    )
    (net (code "44") (name "2V5_ADC_DIG") (class "Default")
      (node (ref "R128") (pin "4") (pinfunction "4_4") (pintype "power_in"))
      (node (ref "U24") (pin "8") (pinfunction "VBUS_8") (pintype "input"))
    )
    (net (code "45") (name "3.3V") (class "Default")
      (node (ref "C163") (pin "1") (pinfunction "1_1") (pintype "passive"))
      (node (ref "C172") (pin "2") (pinfunction "2_2") (pintype "passive"))
      (node (ref "C173") (pin "2") (pinfunction "2_2") (pintype "passive"))
      (node (ref "C174") (pin "2") (pinfunction "2_2") (pintype "passive"))
      (node (ref "C175") (pin "2") (pinfunction "2_2") (pintype "passive"))
      (node (ref "Q18") (pin "2") (pinfunction "E_2") (pintype "passive"))
      (node (ref "Q19") (pin "2") (pinfunction "E_2") (pintype "passive"))
      (node (ref "Q20") (pin "2") (pinfunction "E_2") (pintype "passive"))
      (node (ref "R139") (pin "2") (pinfunction "2_2") (pintype "passive"))
      (node (ref "R163") (pin "2") (pinfunction "2_2") (pintype "passive"))
      (node (ref "R164") (pin "2") (pinfunction "2_2") (pintype "passive"))
      (node (ref "U22") (pin "5") (pinfunction "V+_5") (pintype "power_in"))
      (node (ref "U23") (pin "6") (pinfunction "VS+_6") (pintype "input"))
      (node (ref "U24") (pin "6") (pinfunction "VS+_6") (pintype "input"))
    )
    (net (code "46") (name "3V ADC") (class "Default")
      (node (ref "C176") (pin "1") (pinfunction "1_1") (pintype "passive"))
      (node (ref "C177") (pin "1") (pinfunction "1_1") (pintype "passive"))
      (node (ref "C178") (pin "2") (pinfunction "2_2") (pintype "passive"))
      (node (ref "C179") (pin "1") (pinfunction "1_1") (pintype "passive"))
      (node (ref "C180") (pin "2") (pinfunction "2_2") (pintype "passive"))
      (node (ref "FB8") (pin "2") (pinfunction "2_2") (pintype "passive"))
      (node (ref "U21") (pin "27") (pinfunction "AVDD_27") (pintype "power_in"))
      (node (ref "U21") (pin "32") (pinfunction "AVDD_32") (pintype "power_in"))
    )
    (net (code "47") (name "3V_ADC_ANA") (class "Default")
      (node (ref "R127") (pin "4") (pinfunction "4_4") (pintype "power_in"))
      (node (ref "U23") (pin "8") (pinfunction "VBUS_8") (pintype "input"))
    )
    (net (code "48") (name "ADC_AVDD") (class "Default")
      (node (ref "FB8") (pin "1") (pinfunction "1_1") (pintype "passive"))
      (node (ref "R127") (pin "1") (pinfunction "1_1") (pintype "power_in"))
    )
    (net (code "49") (name "ADC_DVDD") (class "Default")
      (node (ref "FB9") (pin "1") (pinfunction "1_1") (pintype "passive"))
      (node (ref "R128") (pin "1") (pinfunction "1_1") (pintype "power_in"))
    )
    (net (code "50") (name "Net-(D36-A)") (class "Default")
      (node (ref "D36") (pin "2") (pinfunction "A_2") (pintype "passive"))
      (node (ref "Q18") (pin "3") (pinfunction "C_3") (pintype "passive"))
    )
    (net (code "51") (name "Net-(D36-K)") (class "Default")
      (node (ref "D36") (pin "1") (pinfunction "K_1") (pintype "passive"))
      (node (ref "R147") (pin "2") (pinfunction "2_2") (pintype "passive"))
    )
    (net (code "52") (name "Net-(D37-A)") (class "Default")
      (node (ref "D37") (pin "2") (pinfunction "A_2") (pintype "passive"))
      (node (ref "Q20") (pin "3") (pinfunction "C_3") (pintype "passive"))
    )
    (net (code "53") (name "Net-(D37-K)") (class "Default")
      (node (ref "D37") (pin "1") (pinfunction "K_1") (pintype "passive"))
      (node (ref "R169") (pin "2") (pinfunction "2_2") (pintype "passive"))
    )
    (net (code "54") (name "Net-(D38-A)") (class "Default")
      (node (ref "D38") (pin "2") (pinfunction "A_2") (pintype "passive"))
      (node (ref "Q19") (pin "3") (pinfunction "C_3") (pintype "passive"))
    )
    (net (code "55") (name "Net-(D38-K)") (class "Default")
      (node (ref "D38") (pin "1") (pinfunction "K_1") (pintype "passive"))
      (node (ref "R170") (pin "2") (pinfunction "2_2") (pintype "passive"))
    )
    (net (code "56") (name "Net-(Q18-B)") (class "Default")
      (node (ref "Q18") (pin "1") (pinfunction "B_1") (pintype "passive"))
      (node (ref "R139") (pin "1") (pinfunction "1_1") (pintype "passive"))
      (node (ref "R141") (pin "1") (pinfunction "1_1") (pintype "passive"))
    )
    (net (code "57") (name "Net-(Q19-B)") (class "Default")
      (node (ref "Q19") (pin "1") (pinfunction "B_1") (pintype "passive"))
      (node (ref "R164") (pin "1") (pinfunction "1_1") (pintype "passive"))
      (node (ref "R167") (pin "1") (pinfunction "1_1") (pintype "passive"))
    )
    (net (code "58") (name "Net-(Q20-B)") (class "Default")
      (node (ref "Q20") (pin "1") (pinfunction "B_1") (pintype "passive"))
      (node (ref "R163") (pin "1") (pinfunction "1_1") (pintype "passive"))
      (node (ref "R168") (pin "1") (pinfunction "1_1") (pintype "passive"))
    )
    (net (code "59") (name "Net-(U21-REFB)") (class "Default")
      (node (ref "C162") (pin "1") (pinfunction "1_1") (pintype "passive"))
      (node (ref "C164") (pin "2") (pinfunction "2_2") (pintype "passive"))
      (node (ref "C166") (pin "1") (pinfunction "1_1") (pintype "passive"))
      (node (ref "U21") (pin "25") (pinfunction "REFB_25") (pintype "input"))
    )
    (net (code "60") (name "Net-(U21-REFT)") (class "Default")
      (node (ref "C162") (pin "2") (pinfunction "2_2") (pintype "passive"))
      (node (ref "C164") (pin "1") (pinfunction "1_1") (pintype "passive"))
      (node (ref "C165") (pin "1") (pinfunction "1_1") (pintype "passive"))
      (node (ref "U21") (pin "26") (pinfunction "REFT_26") (pintype "input"))
    )
    (net (code "61") (name "Net-(U21-VREF)") (class "Default")
      (node (ref "C167") (pin "1") (pinfunction "1_1") (pintype "passive"))
      (node (ref "C168") (pin "1") (pinfunction "1_1") (pintype "passive"))
      (node (ref "U21") (pin "24") (pinfunction "VREF_24") (pintype "input"))
    )
    (net (code "62") (name "Net-(U22-ALERT)") (class "Default")
      (node (ref "R141") (pin "2") (pinfunction "2_2") (pintype "passive"))
      (node (ref "U22") (pin "3") (pinfunction "ALERT_3") (pintype "open_collector"))
    )
    (net (code "63") (name "Net-(U23-ALERT)") (class "Default")
      (node (ref "R167") (pin "2") (pinfunction "2_2") (pintype "passive"))
      (node (ref "U23") (pin "3") (pinfunction "ALERT_3") (pintype "open_collector"))
    )
    (net (code "64") (name "Net-(U23-VIN+)") (class "Default")
      (node (ref "C170") (pin "1") (pinfunction "1_1") (pintype "passive"))
      (node (ref "R165") (pin "2") (pinfunction "2_2") (pintype "passive"))
      (node (ref "U23") (pin "10") (pinfunction "VIN+_10") (pintype "input"))
    )
    (net (code "65") (name "Net-(U23-VIN-)") (class "Default")
      (node (ref "C170") (pin "2") (pinfunction "2_2") (pintype "passive"))
      (node (ref "R161") (pin "2") (pinfunction "2_2") (pintype "passive"))
      (node (ref "U23") (pin "9") (pinfunction "VIN-_9") (pintype "input"))
    )
    (net (code "66") (name "Net-(U24-ALERT)") (class "Default")
      (node (ref "R168") (pin "2") (pinfunction "2_2") (pintype "passive"))
      (node (ref "U24") (pin "3") (pinfunction "ALERT_3") (pintype "open_collector"))
    )
    (net (code "67") (name "Net-(U24-VIN+)") (class "Default")
      (node (ref "C171") (pin "1") (pinfunction "1_1") (pintype "passive"))
      (node (ref "R166") (pin "2") (pinfunction "2_2") (pintype "passive"))
      (node (ref "U24") (pin "10") (pinfunction "VIN+_10") (pintype "input"))
    )
    (net (code "68") (name "Net-(U24-VIN-)") (class "Default")
      (node (ref "C171") (pin "2") (pinfunction "2_2") (pintype "passive"))
      (node (ref "R162") (pin "2") (pinfunction "2_2") (pintype "passive"))
      (node (ref "U24") (pin "9") (pinfunction "VIN-_9") (pintype "input"))
    )
    (net (code "69") (name "TRB_GND") (class "Default")
      (node (ref "C159") (pin "2") (pinfunction "2_2") (pintype "passive"))
      (node (ref "C160") (pin "2") (pinfunction "2_2") (pintype "passive"))
      (node (ref "C163") (pin "2") (pinfunction "2_2") (pintype "passive"))
      (node (ref "C165") (pin "2") (pinfunction "2_2") (pintype "passive"))
      (node (ref "C166") (pin "2") (pinfunction "2_2") (pintype "passive"))
      (node (ref "C167") (pin "2") (pinfunction "2_2") (pintype "passive"))
      (node (ref "C168") (pin "2") (pinfunction "2_2") (pintype "passive"))
      (node (ref "C172") (pin "1") (pinfunction "1_1") (pintype "passive"))
      (node (ref "C173") (pin "1") (pinfunction "1_1") (pintype "passive"))
      (node (ref "C174") (pin "1") (pinfunction "1_1") (pintype "passive"))
      (node (ref "C175") (pin "1") (pinfunction "1_1") (pintype "passive"))
      (node (ref "C176") (pin "2") (pinfunction "2_2") (pintype "passive"))
      (node (ref "C177") (pin "2") (pinfunction "2_2") (pintype "passive"))
      (node (ref "C178") (pin "1") (pinfunction "1_1") (pintype "passive"))
      (node (ref "C179") (pin "2") (pinfunction "2_2") (pintype "passive"))
      (node (ref "C180") (pin "1") (pinfunction "1_1") (pintype "passive"))
      (node (ref "C181") (pin "1") (pinfunction "1_1") (pintype "passive"))
      (node (ref "C182") (pin "1") (pinfunction "1_1") (pintype "passive"))
      (node (ref "C183") (pin "1") (pinfunction "1_1") (pintype "passive"))
      (node (ref "C184") (pin "2") (pinfunction "2_2") (pintype "passive"))
      (node (ref "C185") (pin "2") (pinfunction "2_2") (pintype "passive"))
      (node (ref "C186") (pin "2") (pinfunction "2_2") (pintype "passive"))
      (node (ref "C187") (pin "2") (pinfunction "2_2") (pintype "passive"))
      (node (ref "C188") (pin "2") (pinfunction "2_2") (pintype "passive"))
      (node (ref "C189") (pin "2") (pinfunction "2_2") (pintype "passive"))
      (node (ref "C190") (pin "1") (pinfunction "1_1") (pintype "passive"))
      (node (ref "C191") (pin "1") (pinfunction "1_1") (pintype "passive"))
      (node (ref "R147") (pin "1") (pinfunction "1_1") (pintype "passive"))
      (node (ref "R169") (pin "1") (pinfunction "1_1") (pintype "passive"))
      (node (ref "R170") (pin "1") (pinfunction "1_1") (pintype "passive"))
      (node (ref "U21") (pin "15") (pinfunction "DGND_15") (pintype "passive"))
      (node (ref "U21") (pin "22") (pinfunction "MODE_22") (pintype "input"))
      (node (ref "U21") (pin "23") (pinfunction "SENSE_23") (pintype "input"))
      (node (ref "U21") (pin "28") (pinfunction "AGND_28") (pintype "passive"))
      (node (ref "U21") (pin "31") (pinfunction "AGND_31") (pintype "passive"))
      (node (ref "U21") (pin "33") (pinfunction "EP_33") (pintype "passive"))
      (node (ref "U21") (pin "4") (pinfunction "PDWN_4") (pintype "input"))
      (node (ref "U22") (pin "2") (pinfunction "GND_2") (pintype "power_in"))
      (node (ref "U23") (pin "7") (pinfunction "GND_7") (pintype "power_in"))
      (node (ref "U24") (pin "1") (pinfunction "A1_1") (pintype "input"))
      (node (ref "U24") (pin "7") (pinfunction "GND_7") (pintype "power_in"))
    )
    (net (code "70") (name "unconnected-(R144-Pad2)") (class "Default")
      (node (ref "R144") (pin "2") (pinfunction "2_2") (pintype "passive"))
    )
    (net (code "71") (name "unconnected-(R145-Pad2)") (class "Default")
      (node (ref "R145") (pin "2") (pinfunction "2_2") (pintype "passive"))
    )
    (net (code "72") (name "unconnected-(R146-Pad2)") (class "Default")
      (node (ref "R146") (pin "2") (pinfunction "2_2") (pintype "passive"))
    )
    (net (code "73") (name "unconnected-(R148-Pad2)") (class "Default")
      (node (ref "R148") (pin "2") (pinfunction "2_2") (pintype "passive"))
    )
    (net (code "74") (name "unconnected-(R149-Pad2)") (class "Default")
      (node (ref "R149") (pin "2") (pinfunction "2_2") (pintype "passive"))
    )
    (net (code "75") (name "unconnected-(R150-Pad2)") (class "Default")
      (node (ref "R150") (pin "2") (pinfunction "2_2") (pintype "passive"))
    )
    (net (code "76") (name "unconnected-(R151-Pad2)") (class "Default")
      (node (ref "R151") (pin "2") (pinfunction "2_2") (pintype "passive"))
    )
    (net (code "77") (name "unconnected-(R152-Pad2)") (class "Default")
      (node (ref "R152") (pin "2") (pinfunction "2_2") (pintype "passive"))
    )
    (net (code "78") (name "unconnected-(R153-Pad2)") (class "Default")
      (node (ref "R153") (pin "2") (pinfunction "2_2") (pintype "passive"))
    )
    (net (code "79") (name "unconnected-(R154-Pad2)") (class "Default")
      (node (ref "R154") (pin "2") (pinfunction "2_2") (pintype "passive"))
    )
    (net (code "80") (name "unconnected-(R157-Pad2)") (class "Default")
      (node (ref "R157") (pin "2") (pinfunction "2_2") (pintype "passive"))
    )
    (net (code "81") (name "unconnected-(R158-Pad2)") (class "Default")
      (node (ref "R158") (pin "2") (pinfunction "2_2") (pintype "passive"))
    )
    (net (code "82") (name "unconnected-(R159-Pad2)") (class "Default")
      (node (ref "R159") (pin "2") (pinfunction "2_2") (pintype "passive"))
    )
    (net (code "83") (name "unconnected-(R160-Pad2)") (class "Default")
      (node (ref "R160") (pin "2") (pinfunction "2_2") (pintype "passive"))
    )
    (net (code "84") (name "unconnected-(U21-DNC-Pad1)") (class "Default")
      (node (ref "U21") (pin "1") (pinfunction "DNC_1") (pintype "passive+no_connect"))
    )
    (net (code "85") (name "unconnected-(U21-DNC-Pad3)") (class "Default")
      (node (ref "U21") (pin "3") (pinfunction "DNC_3") (pintype "passive+no_connect"))
    )
    (net (code "86") (name "unconnected-(U21-OTR-Pad21)") (class "Default")
      (node (ref "U21") (pin "21") (pinfunction "OTR_21") (pintype "output+no_connect"))
    )
  )
)
